# EMG.net
KiCad netlist of a schematic drawn in EAGLE
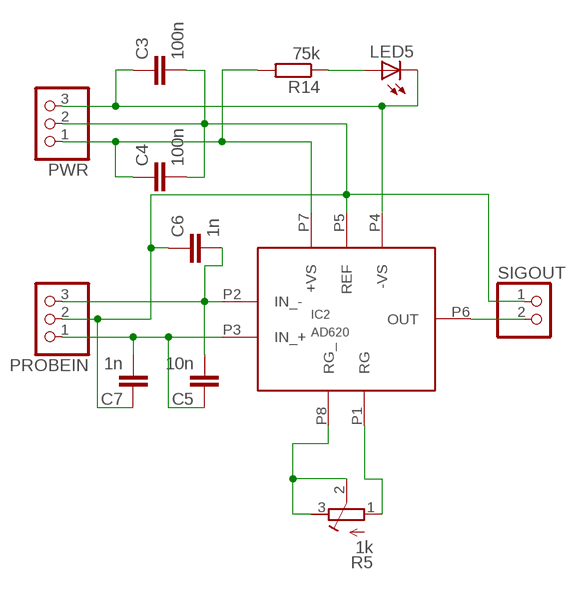
[diagram p0: schematic, sheet 1]

(export (version "E")
  (design (tool "Eeschema 10.0.6"))
  (components
    (comp (ref "C3")
      (value "100n")
      (footprint "eagle-import:C050-025X075")
      (libsource (lib "eagle-import") (part "C-EU050-025X075"))
    )
    (comp (ref "C4")
      (value "100n")
      (footprint "eagle-import:C050-025X075")
      (libsource (lib "eagle-import") (part "C-EU050-025X075"))
    )
    (comp (ref "C5")
      (value "10n")
      (footprint "eagle-import:C050-025X075")
      (libsource (lib "eagle-import") (part "C-EU050-025X075"))
    )
    (comp (ref "C6")
      (value "1n")
      (footprint "eagle-import:C050-024X044")
      (libsource (lib "eagle-import") (part "C-EU050-024X044"))
    )
    (comp (ref "C7")
      (value "1n")
      (footprint "eagle-import:C050-024X044")
      (libsource (lib "eagle-import") (part "C-EU050-024X044"))
    )
    (comp (ref "IC2")
      (value "AD620")
      (footprint "eagle-import:DIL8")
      (libsource (lib "eagle-import") (part "AD620"))
    )
    (comp (ref "LED5")
      (value "LED3MM")
      (footprint "eagle-import:LED3MM")
      (libsource (lib "eagle-import") (part "LED3MM"))
    )
    (comp (ref "PROBEIN")
      (value "PINHD-1X3")
      (footprint "eagle-import:1X03")
      (libsource (lib "eagle-import") (part "PINHD-1X3"))
    )
    (comp (ref "PWR")
      (value "PINHD-1X3")
      (footprint "eagle-import:1X03")
      (libsource (lib "eagle-import") (part "PINHD-1X3"))
    )
    (comp (ref "R5")
      (value "1k")
      (footprint "eagle-import:RTRIM64X")
      (libsource (lib "eagle-import") (part "R-TRIMM64X"))
    )
    (comp (ref "R14")
      (value "75k")
      (footprint "eagle-import:0207_5V")
      (libsource (lib "eagle-import") (part "R-EU_0207/5V"))
    )
    (comp (ref "SIGOUT")
      (value "PINHD-1X2")
      (footprint "eagle-import:1X02")
      (libsource (lib "eagle-import") (part "PINHD-1X2"))
    )
  )
  (nets
    (net (code "1") (name "Net-(IC2-+VS)") (class "Default")
      (node (ref "C4") (pin "1") (pinfunction "1_1") (pintype "passive"))
      (node (ref "IC2") (pin "P7") (pinfunction "+VS_P7") (pintype "power_in"))
      (node (ref "PWR") (pin "1") (pinfunction "1_1") (pintype "passive"))
      (node (ref "R14") (pin "2") (pinfunction "2_2") (pintype "passive"))
    )
    (net (code "2") (name "Net-(IC2--VS)") (class "Default")
      (node (ref "C3") (pin "1") (pinfunction "1_1") (pintype "passive"))
      (node (ref "IC2") (pin "P4") (pinfunction "-VS_P4") (pintype "power_in"))
      (node (ref "LED5") (pin "K") (pinfunction "C_K") (pintype "passive"))
      (node (ref "PWR") (pin "3") (pinfunction "3_3") (pintype "passive"))
    )
    (net (code "3") (name "Net-(IC2-IN_+)") (class "Default")
      (node (ref "C5") (pin "1") (pinfunction "1_1") (pintype "passive"))
      (node (ref "C7") (pin "2") (pinfunction "2_2") (pintype "passive"))
      (node (ref "IC2") (pin "P3") (pinfunction "IN_+_P3") (pintype "input"))
      (node (ref "PROBEIN") (pin "1") (pinfunction "1_1") (pintype "passive"))
    )
    (net (code "4") (name "Net-(IC2-IN_-)") (class "Default")
      (node (ref "C5") (pin "2") (pinfunction "2_2") (pintype "passive"))
      (node (ref "C6") (pin "2") (pinfunction "2_2") (pintype "passive"))
      (node (ref "IC2") (pin "P2") (pinfunction "IN_-_P2") (pintype "input"))
      (node (ref "PROBEIN") (pin "3") (pinfunction "3_3") (pintype "passive"))
    )
    (net (code "5") (name "Net-(IC2-OUT)") (class "Default")
      (node (ref "IC2") (pin "P6") (pinfunction "OUT_P6") (pintype "output"))
      (node (ref "SIGOUT") (pin "2") (pinfunction "2_2") (pintype "passive"))
    )
    (net (code "6") (name "Net-(IC2-REF)") (class "Default")
      (node (ref "C3") (pin "2") (pinfunction "2_2") (pintype "passive"))
      (node (ref "C4") (pin "2") (pinfunction "2_2") (pintype "passive"))
      (node (ref "C6") (pin "1") (pinfunction "1_1") (pintype "passive"))
      (node (ref "C7") (pin "1") (pinfunction "1_1") (pintype "passive"))
      (node (ref "IC2") (pin "P5") (pinfunction "REF_P5") (pintype "power_in"))
      (node (ref "PROBEIN") (pin "2") (pinfunction "2_2") (pintype "passive"))
      (node (ref "PWR") (pin "2") (pinfunction "2_2") (pintype "passive"))
      (node (ref "SIGOUT") (pin "1") (pinfunction "1_1") (pintype "passive"))
    )
    (net (code "7") (name "Net-(IC2-RG)") (class "Default")
      (node (ref "IC2") (pin "P1") (pinfunction "RG_P1") (pintype "input"))
      (node (ref "R5") (pin "1") (pinfunction "A_1") (pintype "passive"))
    )
    (net (code "8") (name "Net-(IC2-RG_)") (class "Default")
      (node (ref "IC2") (pin "P8") (pinfunction "RG__P8") (pintype "input"))
      (node (ref "R5") (pin "2") (pinfunction "S_2") (pintype "passive"))
      (node (ref "R5") (pin "3") (pinfunction "E_3") (pintype "passive"))
    )
    (net (code "9") (name "Net-(LED5-PadA)") (class "Default")
      (node (ref "LED5") (pin "A") (pinfunction "A_A") (pintype "passive"))
      (node (ref "R14") (pin "1") (pinfunction "1_1") (pintype "passive"))
    )
  )
)
